# TFT_BORAD.net
KiCad netlist of a schematic drawn in Altium Designer
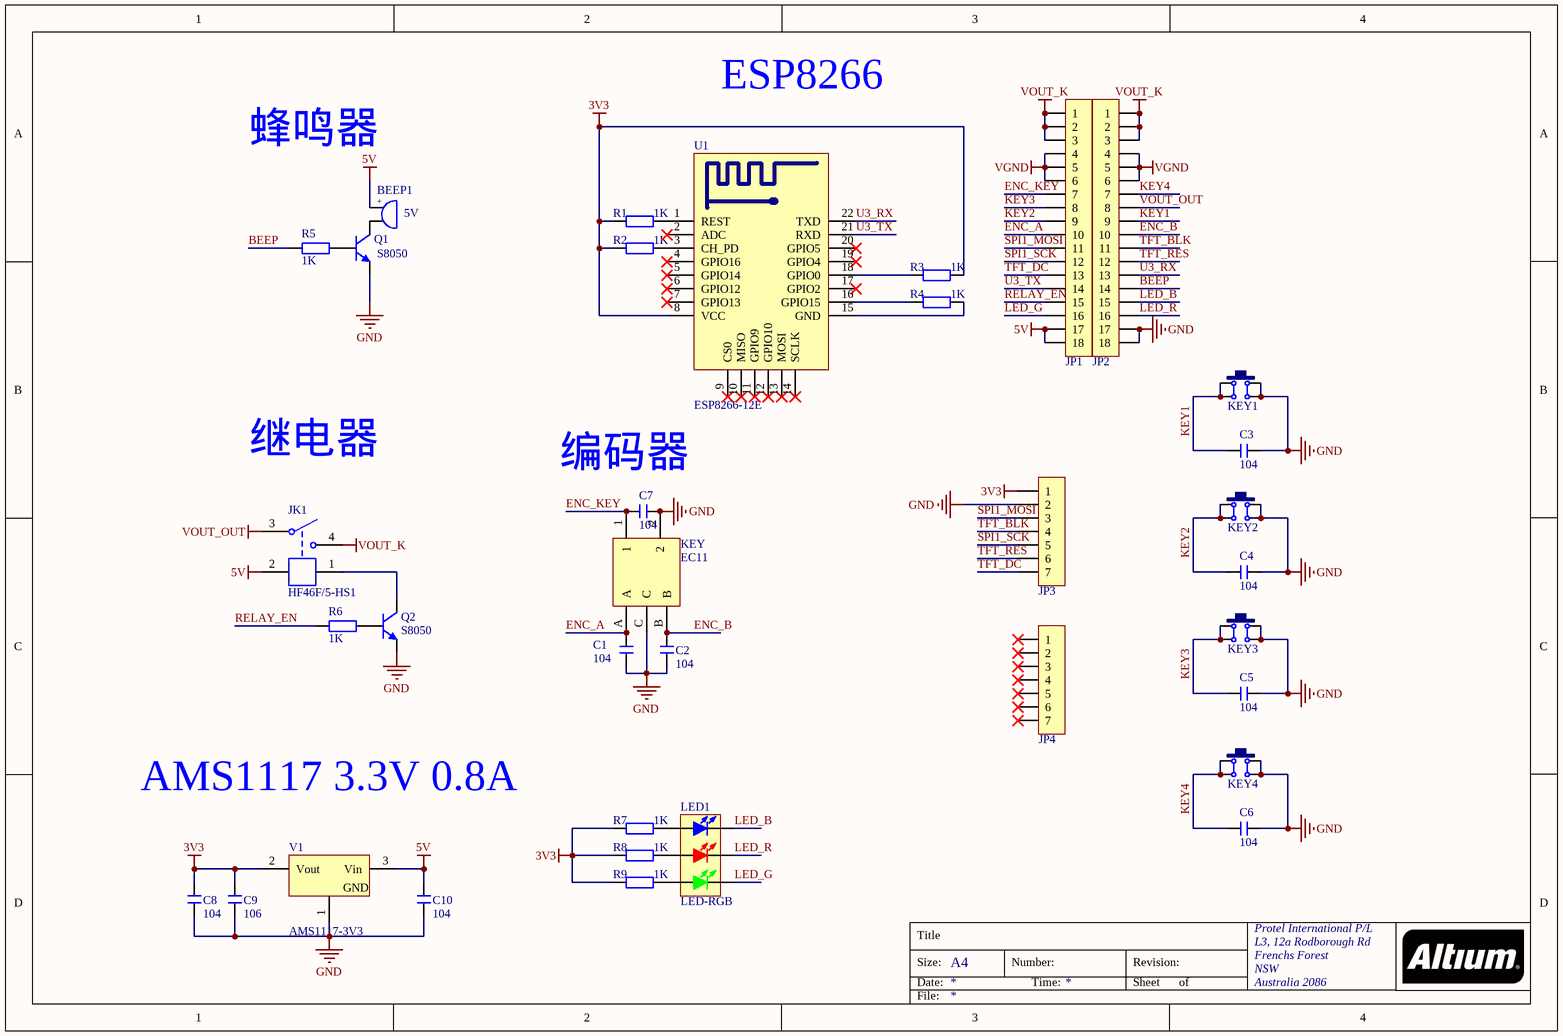
[diagram p0: TFT_BORAD.SchDoc]

(export (version "E")
  (design (tool "Eeschema 10.0.6"))
  (components
    (comp (ref "BEEP1")
      (value "5V")
      (footprint "BEEP 6.5x12x8.5")
      (description "蜂鸣器")
      (fields (field (name "版权归属") "源创客"))
      (libsource (lib "15.1 - 未分类器件") (part "BEEP"))
    )
    (comp (ref "C1")
      (value "104")
      (footprint "C 0603_M")
      (description "无极性贴片电容")
      (fields (field (name "版权归属") "源创客"))
      (libsource (lib "3.1   - 电阻-电容-电感") (part "C"))
    )
    (comp (ref "C2")
      (value "104")
      (footprint "C 0603_M")
      (description "无极性贴片电容")
      (fields (field (name "版权归属") "源创客"))
      (libsource (lib "3.1   - 电阻-电容-电感") (part "C"))
    )
    (comp (ref "C3")
      (value "104")
      (footprint "C 0603_M")
      (description "无极性贴片电容")
      (fields (field (name "版权归属") "源创客"))
      (libsource (lib "3.1   - 电阻-电容-电感") (part "C"))
    )
    (comp (ref "C4")
      (value "104")
      (footprint "C 0603_M")
      (description "无极性贴片电容")
      (fields (field (name "版权归属") "源创客"))
      (libsource (lib "3.1   - 电阻-电容-电感") (part "C"))
    )
    (comp (ref "C5")
      (value "104")
      (footprint "C 0603_M")
      (description "无极性贴片电容")
      (fields (field (name "版权归属") "源创客"))
      (libsource (lib "3.1   - 电阻-电容-电感") (part "C"))
    )
    (comp (ref "C6")
      (value "104")
      (footprint "C 0603_M")
      (description "无极性贴片电容")
      (fields (field (name "版权归属") "源创客"))
      (libsource (lib "3.1   - 电阻-电容-电感") (part "C"))
    )
    (comp (ref "C7")
      (value "104")
      (footprint "C 0603_M")
      (description "无极性贴片电容")
      (fields (field (name "版权归属") "源创客"))
      (libsource (lib "3.1   - 电阻-电容-电感") (part "C"))
    )
    (comp (ref "C8")
      (value "104")
      (footprint "C 0603_M")
      (description "无极性贴片电容")
      (fields (field (name "版权归属") "源创客"))
      (libsource (lib "3.1   - 电阻-电容-电感") (part "C"))
    )
    (comp (ref "C9")
      (value "106")
      (footprint "C 0603_M")
      (description "无极性贴片电容")
      (fields (field (name "版权归属") "源创客"))
      (libsource (lib "3.1   - 电阻-电容-电感") (part "C"))
    )
    (comp (ref "C10")
      (value "104")
      (footprint "C 0603_M")
      (description "无极性贴片电容")
      (fields (field (name "版权归属") "源创客"))
      (libsource (lib "3.1   - 电阻-电容-电感") (part "C"))
    )
    (comp (ref "JK1")
      (value "HF46F/5-HS1")
      (footprint "HF46-xx-HS1")
      (description "5V一组常开")
      (fields (field (name "版权归属") "源创客"))
      (libsource (lib "7.1   - 继电器") (part "HF46F/5-HS1"))
    )
    (comp (ref "JP1")
      (value "HDR-1X18")
      (footprint "HDR2.54-M-LI-18P")
      (description "18P接插件")
      (fields (field (name "版权归属") "源创客"))
      (libsource (lib "") (part "Header 18_1"))
    )
    (comp (ref "JP2")
      (value "HDR-1X18")
      (footprint "HDR2.54-M-LI-18P")
      (description "18P接插件")
      (fields (field (name "版权归属") "源创客"))
      (libsource (lib "4.5   - 接插件-脚距2.54") (part "Header 18"))
    )
    (comp (ref "JP3")
      (value "HDR-1X7")
      (footprint "HDR2.54-LI-7P")
      (description "7P接插件")
      (fields (field (name "版权归属") "源创客"))
      (libsource (lib "4.5   - 接插件-脚距2.54") (part "Header 7"))
    )
    (comp (ref "JP4")
      (value "HDR-1X7")
      (footprint "HDR2.54-LI-7P")
      (description "7P接插件")
      (fields (field (name "版权归属") "源创客"))
      (libsource (lib "4.5   - 接插件-脚距2.54") (part "Header 7"))
    )
    (comp (ref "KEY")
      (value "EC11")
      (footprint "EC11")
      (description "数字开关编码器")
      (fields (field (name "版权归属") "源创客"))
      (libsource (lib "5.1   - 按键-开关") (part "EC11"))
    )
    (comp (ref "KEY1")
      (value "6x6x5")
      (footprint "TSW DIP-6*6*10")
      (description "直插6x6轻触开关")
      (fields (field (name "版权归属") "源创客"))
      (libsource (lib "5.1   - 按键-开关") (part "TSW DIP-6x6"))
    )
    (comp (ref "KEY2")
      (value "6x6x5")
      (footprint "TSW DIP-6*6*10")
      (description "直插6x6轻触开关")
      (fields (field (name "版权归属") "源创客"))
      (libsource (lib "5.1   - 按键-开关") (part "TSW DIP-6x6"))
    )
    (comp (ref "KEY3")
      (value "6x6x5")
      (footprint "TSW DIP-6*6*10")
      (description "直插6x6轻触开关")
      (fields (field (name "版权归属") "源创客"))
      (libsource (lib "5.1   - 按键-开关") (part "TSW DIP-6x6"))
    )
    (comp (ref "KEY4")
      (value "6x6x5")
      (footprint "TSW DIP-6*6*10")
      (description "直插6x6轻触开关")
      (fields (field (name "版权归属") "源创客"))
      (libsource (lib "5.1   - 按键-开关") (part "TSW DIP-6x6"))
    )
    (comp (ref "LED1")
      (value "LED-RGB")
      (footprint "LED 5050")
      (description "三基色LED")
      (fields (field (name "版权归属") "源创客"))
      (libsource (lib "9.1   - LED") (part "LED-RGB"))
    )
    (comp (ref "Q1")
      (value "S8050")
      (footprint "SOT23-3M")
      (description "高频放大-NPN型")
      (fields (field (name "版权归属") "源创客"))
      (libsource (lib "6.2   - 三极管") (part "8050-SMD"))
    )
    (comp (ref "Q2")
      (value "S8050")
      (footprint "SOT23-3M")
      (description "高频放大-NPN型")
      (fields (field (name "版权归属") "源创客"))
      (libsource (lib "6.2   - 三极管") (part "8050-SMD"))
    )
    (comp (ref "R1")
      (value "1K")
      (footprint "R 0603_M")
      (description "贴片电阻")
      (fields (field (name "版权归属") "源创客"))
      (libsource (lib "3.1   - 电阻-电容-电感") (part "R"))
    )
    (comp (ref "R2")
      (value "1K")
      (footprint "R 0603_M")
      (description "贴片电阻")
      (fields (field (name "版权归属") "源创客"))
      (libsource (lib "3.1   - 电阻-电容-电感") (part "R"))
    )
    (comp (ref "R3")
      (value "1K")
      (footprint "R 0603_M")
      (description "贴片电阻")
      (fields (field (name "版权归属") "源创客"))
      (libsource (lib "3.1   - 电阻-电容-电感") (part "R"))
    )
    (comp (ref "R4")
      (value "1K")
      (footprint "R 0603_M")
      (description "贴片电阻")
      (fields (field (name "版权归属") "源创客"))
      (libsource (lib "3.1   - 电阻-电容-电感") (part "R"))
    )
    (comp (ref "R5")
      (value "1K")
      (footprint "R 0603_M")
      (description "贴片电阻")
      (fields (field (name "版权归属") "源创客"))
      (libsource (lib "3.1   - 电阻-电容-电感") (part "R"))
    )
    (comp (ref "R6")
      (value "1K")
      (footprint "R 0603_M")
      (description "贴片电阻")
      (fields (field (name "版权归属") "源创客"))
      (libsource (lib "3.1   - 电阻-电容-电感") (part "R"))
    )
    (comp (ref "R7")
      (value "1K")
      (footprint "R 0603_M")
      (description "贴片电阻")
      (fields (field (name "版权归属") "源创客"))
      (libsource (lib "3.1   - 电阻-电容-电感") (part "R"))
    )
    (comp (ref "R8")
      (value "1K")
      (footprint "R 0603_M")
      (description "贴片电阻")
      (fields (field (name "版权归属") "源创客"))
      (libsource (lib "3.1   - 电阻-电容-电感") (part "R"))
    )
    (comp (ref "R9")
      (value "1K")
      (footprint "R 0603_M")
      (description "贴片电阻")
      (fields (field (name "版权归属") "源创客"))
      (libsource (lib "3.1   - 电阻-电容-电感") (part "R"))
    )
    (comp (ref "U1")
      (value "ESP8266-12E")
      (footprint "ESP_12E")
      (description "串口 WIFI模块，ESP-12E")
      (fields (field (name "版权归属") "源创客"))
      (libsource (lib "13.1 - 模块") (part "ESP8266-12E"))
    )
    (comp (ref "V1")
      (value "AMS1117-3V3")
      (footprint "SOT223_L")
      (description "三端稳压芯片")
      (fields (field (name "版权归属") "源创客"))
      (libsource (lib "1.3   - 电源类芯片") (part "AMS1117"))
    )
  )
  (nets
    (net (code "1") (name "/BEEP") (class "Default")
      (node (ref "JP2") (pin "14") (pinfunction "14_14") (pintype "passive"))
      (node (ref "R5") (pin "2") (pinfunction "2_2") (pintype "passive"))
    )
    (net (code "2") (name "/ENC_A") (class "Default")
      (node (ref "C1") (pin "1") (pinfunction "1_1") (pintype "passive"))
      (node (ref "JP1") (pin "10") (pinfunction "10_10") (pintype "passive"))
      (node (ref "KEY") (pin "A") (pinfunction "A_A") (pintype "passive"))
    )
    (net (code "3") (name "/ENC_B") (class "Default")
      (node (ref "C2") (pin "1") (pinfunction "1_1") (pintype "passive"))
      (node (ref "JP2") (pin "10") (pinfunction "10_10") (pintype "passive"))
      (node (ref "KEY") (pin "B") (pinfunction "B_B") (pintype "passive"))
    )
    (net (code "4") (name "/ENC_KEY") (class "Default")
      (node (ref "C7") (pin "1") (pinfunction "1_1") (pintype "passive"))
      (node (ref "JP1") (pin "7") (pinfunction "7_7") (pintype "passive"))
      (node (ref "KEY") (pin "1") (pinfunction "1_1") (pintype "passive"))
    )
    (net (code "5") (name "/KEY1") (class "Default")
      (node (ref "C3") (pin "1") (pinfunction "1_1") (pintype "passive"))
      (node (ref "JP2") (pin "9") (pinfunction "9_9") (pintype "passive"))
      (node (ref "KEY1") (pin "1") (pinfunction "1_1") (pintype "passive"))
      (node (ref "KEY1") (pin "4") (pinfunction "4_4") (pintype "passive"))
    )
    (net (code "6") (name "/KEY2") (class "Default")
      (node (ref "C4") (pin "1") (pinfunction "1_1") (pintype "passive"))
      (node (ref "JP1") (pin "9") (pinfunction "9_9") (pintype "passive"))
      (node (ref "KEY2") (pin "1") (pinfunction "1_1") (pintype "passive"))
      (node (ref "KEY2") (pin "4") (pinfunction "4_4") (pintype "passive"))
    )
    (net (code "7") (name "/KEY3") (class "Default")
      (node (ref "C5") (pin "1") (pinfunction "1_1") (pintype "passive"))
      (node (ref "JP1") (pin "8") (pinfunction "8_8") (pintype "passive"))
      (node (ref "KEY3") (pin "1") (pinfunction "1_1") (pintype "passive"))
      (node (ref "KEY3") (pin "4") (pinfunction "4_4") (pintype "passive"))
    )
    (net (code "8") (name "/KEY4") (class "Default")
      (node (ref "C6") (pin "1") (pinfunction "1_1") (pintype "passive"))
      (node (ref "JP2") (pin "7") (pinfunction "7_7") (pintype "passive"))
      (node (ref "KEY4") (pin "1") (pinfunction "1_1") (pintype "passive"))
      (node (ref "KEY4") (pin "4") (pinfunction "4_4") (pintype "passive"))
    )
    (net (code "9") (name "/LED_B") (class "Default")
      (node (ref "JP2") (pin "15") (pinfunction "15_15") (pintype "passive"))
      (node (ref "LED1") (pin "6") (pinfunction "BULE_K_6") (pintype "passive"))
    )
    (net (code "10") (name "/LED_G") (class "Default")
      (node (ref "JP1") (pin "16") (pinfunction "16_16") (pintype "passive"))
      (node (ref "LED1") (pin "4") (pinfunction "GREEN_K_4") (pintype "passive"))
    )
    (net (code "11") (name "/LED_R") (class "Default")
      (node (ref "JP2") (pin "16") (pinfunction "16_16") (pintype "passive"))
      (node (ref "LED1") (pin "5") (pinfunction "RED_K_5") (pintype "passive"))
    )
    (net (code "12") (name "/RELAY_EN") (class "Default")
      (node (ref "JP1") (pin "15") (pinfunction "15_15") (pintype "passive"))
      (node (ref "R6") (pin "2") (pinfunction "2_2") (pintype "passive"))
    )
    (net (code "13") (name "/SPI1_MOSI") (class "Default")
      (node (ref "JP1") (pin "11") (pinfunction "11_11") (pintype "passive"))
      (node (ref "JP3") (pin "3") (pinfunction "3_3") (pintype "passive"))
    )
    (net (code "14") (name "/SPI1_SCK") (class "Default")
      (node (ref "JP1") (pin "12") (pinfunction "12_12") (pintype "passive"))
      (node (ref "JP3") (pin "5") (pinfunction "5_5") (pintype "passive"))
    )
    (net (code "15") (name "/TFT_BLK") (class "Default")
      (node (ref "JP2") (pin "11") (pinfunction "11_11") (pintype "passive"))
      (node (ref "JP3") (pin "4") (pinfunction "4_4") (pintype "passive"))
    )
    (net (code "16") (name "/TFT_DC") (class "Default")
      (node (ref "JP1") (pin "13") (pinfunction "13_13") (pintype "passive"))
      (node (ref "JP3") (pin "7") (pinfunction "7_7") (pintype "passive"))
    )
    (net (code "17") (name "/TFT_RES") (class "Default")
      (node (ref "JP2") (pin "12") (pinfunction "12_12") (pintype "passive"))
      (node (ref "JP3") (pin "6") (pinfunction "6_6") (pintype "passive"))
    )
    (net (code "18") (name "/U3_RX") (class "Default")
      (node (ref "JP2") (pin "13") (pinfunction "13_13") (pintype "passive"))
      (node (ref "U1") (pin "22") (pinfunction "TXD_22") (pintype "passive"))
    )
    (net (code "19") (name "/U3_TX") (class "Default")
      (node (ref "JP1") (pin "14") (pinfunction "14_14") (pintype "passive"))
      (node (ref "U1") (pin "21") (pinfunction "RXD_21") (pintype "passive"))
    )
    (net (code "20") (name "3V3") (class "Default")
      (node (ref "C8") (pin "2") (pinfunction "2_2") (pintype "passive"))
      (node (ref "C9") (pin "2") (pinfunction "2_2") (pintype "passive"))
      (node (ref "JP3") (pin "1") (pinfunction "1_1") (pintype "passive"))
      (node (ref "R1") (pin "1") (pinfunction "1_1") (pintype "passive"))
      (node (ref "R2") (pin "1") (pinfunction "1_1") (pintype "passive"))
      (node (ref "R4") (pin "2") (pinfunction "2_2") (pintype "passive"))
      (node (ref "R7") (pin "2") (pinfunction "2_2") (pintype "passive"))
      (node (ref "R8") (pin "2") (pinfunction "2_2") (pintype "passive"))
      (node (ref "R9") (pin "2") (pinfunction "2_2") (pintype "passive"))
      (node (ref "U1") (pin "8") (pinfunction "VCC_8") (pintype "passive"))
      (node (ref "V1") (pin "2") (pinfunction "Vout_2") (pintype "passive"))
    )
    (net (code "21") (name "5V") (class "Default")
      (node (ref "BEEP1") (pin "1") (pinfunction "1_1") (pintype "passive"))
      (node (ref "C10") (pin "2") (pinfunction "2_2") (pintype "passive"))
      (node (ref "JK1") (pin "2") (pinfunction "2_2") (pintype "passive"))
      (node (ref "JP1") (pin "17") (pinfunction "17_17") (pintype "passive"))
      (node (ref "JP1") (pin "18") (pinfunction "18_18") (pintype "passive"))
      (node (ref "V1") (pin "3") (pinfunction "Vin_3") (pintype "passive"))
    )
    (net (code "22") (name "GND") (class "Default")
      (node (ref "C1") (pin "2") (pinfunction "2_2") (pintype "passive"))
      (node (ref "C10") (pin "1") (pinfunction "1_1") (pintype "passive"))
      (node (ref "C2") (pin "2") (pinfunction "2_2") (pintype "passive"))
      (node (ref "C3") (pin "2") (pinfunction "2_2") (pintype "passive"))
      (node (ref "C4") (pin "2") (pinfunction "2_2") (pintype "passive"))
      (node (ref "C5") (pin "2") (pinfunction "2_2") (pintype "passive"))
      (node (ref "C6") (pin "2") (pinfunction "2_2") (pintype "passive"))
      (node (ref "C7") (pin "2") (pinfunction "2_2") (pintype "passive"))
      (node (ref "C8") (pin "1") (pinfunction "1_1") (pintype "passive"))
      (node (ref "C9") (pin "1") (pinfunction "1_1") (pintype "passive"))
      (node (ref "JP2") (pin "17") (pinfunction "17_17") (pintype "passive"))
      (node (ref "JP2") (pin "18") (pinfunction "18_18") (pintype "passive"))
      (node (ref "JP3") (pin "2") (pinfunction "2_2") (pintype "passive"))
      (node (ref "KEY") (pin "2") (pinfunction "2_2") (pintype "passive"))
      (node (ref "KEY") (pin "C") (pinfunction "C_C") (pintype "passive"))
      (node (ref "KEY1") (pin "2") (pinfunction "2_2") (pintype "passive"))
      (node (ref "KEY1") (pin "3") (pinfunction "3_3") (pintype "passive"))
      (node (ref "KEY2") (pin "2") (pinfunction "2_2") (pintype "passive"))
      (node (ref "KEY2") (pin "3") (pinfunction "3_3") (pintype "passive"))
      (node (ref "KEY3") (pin "2") (pinfunction "2_2") (pintype "passive"))
      (node (ref "KEY3") (pin "3") (pinfunction "3_3") (pintype "passive"))
      (node (ref "KEY4") (pin "2") (pinfunction "2_2") (pintype "passive"))
      (node (ref "KEY4") (pin "3") (pinfunction "3_3") (pintype "passive"))
      (node (ref "Q1") (pin "2") (pinfunction "E_2") (pintype "passive"))
      (node (ref "Q2") (pin "2") (pinfunction "E_2") (pintype "passive"))
      (node (ref "V1") (pin "1") (pinfunction "GND_1") (pintype "passive"))
    )
    (net (code "23") (name "Net-(LED1-BULE_A)") (class "Default")
      (node (ref "LED1") (pin "1") (pinfunction "BULE_A_1") (pintype "passive"))
      (node (ref "R7") (pin "1") (pinfunction "1_1") (pintype "passive"))
    )
    (net (code "24") (name "Net-(LED1-GREEN_A)") (class "Default")
      (node (ref "LED1") (pin "3") (pinfunction "GREEN_A_3") (pintype "passive"))
      (node (ref "R9") (pin "1") (pinfunction "1_1") (pintype "passive"))
    )
    (net (code "25") (name "Net-(LED1-RED_A)") (class "Default")
      (node (ref "LED1") (pin "2") (pinfunction "RED_A_2") (pintype "passive"))
      (node (ref "R8") (pin "1") (pinfunction "1_1") (pintype "passive"))
    )
    (net (code "26") (name "Net-(Q1-B)") (class "Default")
      (node (ref "Q1") (pin "1") (pinfunction "B_1") (pintype "passive"))
      (node (ref "R5") (pin "1") (pinfunction "1_1") (pintype "passive"))
    )
    (net (code "27") (name "Net-(Q1-C)") (class "Default")
      (node (ref "BEEP1") (pin "2") (pinfunction "2_2") (pintype "passive"))
      (node (ref "Q1") (pin "3") (pinfunction "C_3") (pintype "passive"))
    )
    (net (code "28") (name "Net-(Q2-B)") (class "Default")
      (node (ref "Q2") (pin "1") (pinfunction "B_1") (pintype "passive"))
      (node (ref "R6") (pin "1") (pinfunction "1_1") (pintype "passive"))
    )
    (net (code "29") (name "Net-(Q2-C)") (class "Default")
      (node (ref "JK1") (pin "1") (pinfunction "1_1") (pintype "passive"))
      (node (ref "Q2") (pin "3") (pinfunction "C_3") (pintype "passive"))
    )
    (net (code "30") (name "Net-(U1-CH_PD)") (class "Default")
      (node (ref "R2") (pin "2") (pinfunction "2_2") (pintype "passive"))
      (node (ref "U1") (pin "3") (pinfunction "CH_PD_3") (pintype "passive"))
    )
    (net (code "31") (name "Net-(U1-GND)") (class "Default")
      (node (ref "R3") (pin "2") (pinfunction "2_2") (pintype "passive"))
      (node (ref "U1") (pin "15") (pinfunction "GND_15") (pintype "passive"))
    )
    (net (code "32") (name "Net-(U1-GPIO0)") (class "Default")
      (node (ref "R4") (pin "1") (pinfunction "1_1") (pintype "passive"))
      (node (ref "U1") (pin "18") (pinfunction "GPIO0_18") (pintype "passive"))
    )
    (net (code "33") (name "Net-(U1-GPIO15)") (class "Default")
      (node (ref "R3") (pin "1") (pinfunction "1_1") (pintype "passive"))
      (node (ref "U1") (pin "16") (pinfunction "GPIO15_16") (pintype "passive"))
    )
    (net (code "34") (name "Net-(U1-REST)") (class "Default")
      (node (ref "R1") (pin "2") (pinfunction "2_2") (pintype "passive"))
      (node (ref "U1") (pin "1") (pinfunction "REST_1") (pintype "passive"))
    )
    (net (code "35") (name "VGND") (class "Default")
      (node (ref "JP1") (pin "4") (pinfunction "4_4") (pintype "passive"))
      (node (ref "JP1") (pin "5") (pinfunction "5_5") (pintype "passive"))
      (node (ref "JP1") (pin "6") (pinfunction "6_6") (pintype "passive"))
      (node (ref "JP2") (pin "4") (pinfunction "4_4") (pintype "passive"))
      (node (ref "JP2") (pin "5") (pinfunction "5_5") (pintype "passive"))
      (node (ref "JP2") (pin "6") (pinfunction "6_6") (pintype "passive"))
    )
    (net (code "36") (name "VOUT_K") (class "Default")
      (node (ref "JK1") (pin "4") (pinfunction "4_4") (pintype "passive"))
      (node (ref "JP1") (pin "1") (pinfunction "1_1") (pintype "passive"))
      (node (ref "JP1") (pin "2") (pinfunction "2_2") (pintype "passive"))
      (node (ref "JP1") (pin "3") (pinfunction "3_3") (pintype "passive"))
      (node (ref "JP2") (pin "1") (pinfunction "1_1") (pintype "passive"))
      (node (ref "JP2") (pin "2") (pinfunction "2_2") (pintype "passive"))
      (node (ref "JP2") (pin "3") (pinfunction "3_3") (pintype "passive"))
    )
    (net (code "37") (name "VOUT_OUT") (class "Default")
      (node (ref "JK1") (pin "3") (pinfunction "3_3") (pintype "passive"))
      (node (ref "JP2") (pin "8") (pinfunction "8_8") (pintype "passive"))
    )
    (net (code "38") (name "unconnected-(JP4-Pad1)") (class "Default")
      (node (ref "JP4") (pin "1") (pinfunction "1_1") (pintype "passive+no_connect"))
    )
    (net (code "39") (name "unconnected-(JP4-Pad2)") (class "Default")
      (node (ref "JP4") (pin "2") (pinfunction "2_2") (pintype "passive+no_connect"))
    )
    (net (code "40") (name "unconnected-(JP4-Pad3)") (class "Default")
      (node (ref "JP4") (pin "3") (pinfunction "3_3") (pintype "passive+no_connect"))
    )
    (net (code "41") (name "unconnected-(JP4-Pad4)") (class "Default")
      (node (ref "JP4") (pin "4") (pinfunction "4_4") (pintype "passive+no_connect"))
    )
    (net (code "42") (name "unconnected-(JP4-Pad5)") (class "Default")
      (node (ref "JP4") (pin "5") (pinfunction "5_5") (pintype "passive+no_connect"))
    )
    (net (code "43") (name "unconnected-(JP4-Pad6)") (class "Default")
      (node (ref "JP4") (pin "6") (pinfunction "6_6") (pintype "passive+no_connect"))
    )
    (net (code "44") (name "unconnected-(JP4-Pad7)") (class "Default")
      (node (ref "JP4") (pin "7") (pinfunction "7_7") (pintype "passive+no_connect"))
    )
    (net (code "45") (name "unconnected-(U1-ADC-Pad2)") (class "Default")
      (node (ref "U1") (pin "2") (pinfunction "ADC_2") (pintype "passive+no_connect"))
    )
    (net (code "46") (name "unconnected-(U1-CS0-Pad9)") (class "Default")
      (node (ref "U1") (pin "9") (pinfunction "CS0_9") (pintype "passive+no_connect"))
    )
    (net (code "47") (name "unconnected-(U1-GPIO2-Pad17)") (class "Default")
      (node (ref "U1") (pin "17") (pinfunction "GPIO2_17") (pintype "passive+no_connect"))
    )
    (net (code "48") (name "unconnected-(U1-GPIO4-Pad19)") (class "Default")
      (node (ref "U1") (pin "19") (pinfunction "GPIO4_19") (pintype "passive+no_connect"))
    )
    (net (code "49") (name "unconnected-(U1-GPIO5-Pad20)") (class "Default")
      (node (ref "U1") (pin "20") (pinfunction "GPIO5_20") (pintype "passive+no_connect"))
    )
    (net (code "50") (name "unconnected-(U1-GPIO9-Pad11)") (class "Default")
      (node (ref "U1") (pin "11") (pinfunction "GPIO9_11") (pintype "passive+no_connect"))
    )
    (net (code "51") (name "unconnected-(U1-GPIO10-Pad12)") (class "Default")
      (node (ref "U1") (pin "12") (pinfunction "GPIO10_12") (pintype "passive+no_connect"))
    )
    (net (code "52") (name "unconnected-(U1-GPIO12-Pad6)") (class "Default")
      (node (ref "U1") (pin "6") (pinfunction "GPIO12_6") (pintype "passive+no_connect"))
    )
    (net (code "53") (name "unconnected-(U1-GPIO13-Pad7)") (class "Default")
      (node (ref "U1") (pin "7") (pinfunction "GPIO13_7") (pintype "passive+no_connect"))
    )
    (net (code "54") (name "unconnected-(U1-GPIO14-Pad5)") (class "Default")
      (node (ref "U1") (pin "5") (pinfunction "GPIO14_5") (pintype "passive+no_connect"))
    )
    (net (code "55") (name "unconnected-(U1-GPIO16-Pad4)") (class "Default")
      (node (ref "U1") (pin "4") (pinfunction "GPIO16_4") (pintype "passive+no_connect"))
    )
    (net (code "56") (name "unconnected-(U1-MISO-Pad10)") (class "Default")
      (node (ref "U1") (pin "10") (pinfunction "MISO_10") (pintype "passive+no_connect"))
    )
    (net (code "57") (name "unconnected-(U1-MOSI-Pad13)") (class "Default")
      (node (ref "U1") (pin "13") (pinfunction "MOSI_13") (pintype "passive+no_connect"))
    )
    (net (code "58") (name "unconnected-(U1-SCLK-Pad14)") (class "Default")
      (node (ref "U1") (pin "14") (pinfunction "SCLK_14") (pintype "passive+no_connect"))
    )
  )
)
